# optic_fiber.net
KiCad netlist of a schematic drawn in Altium Designer
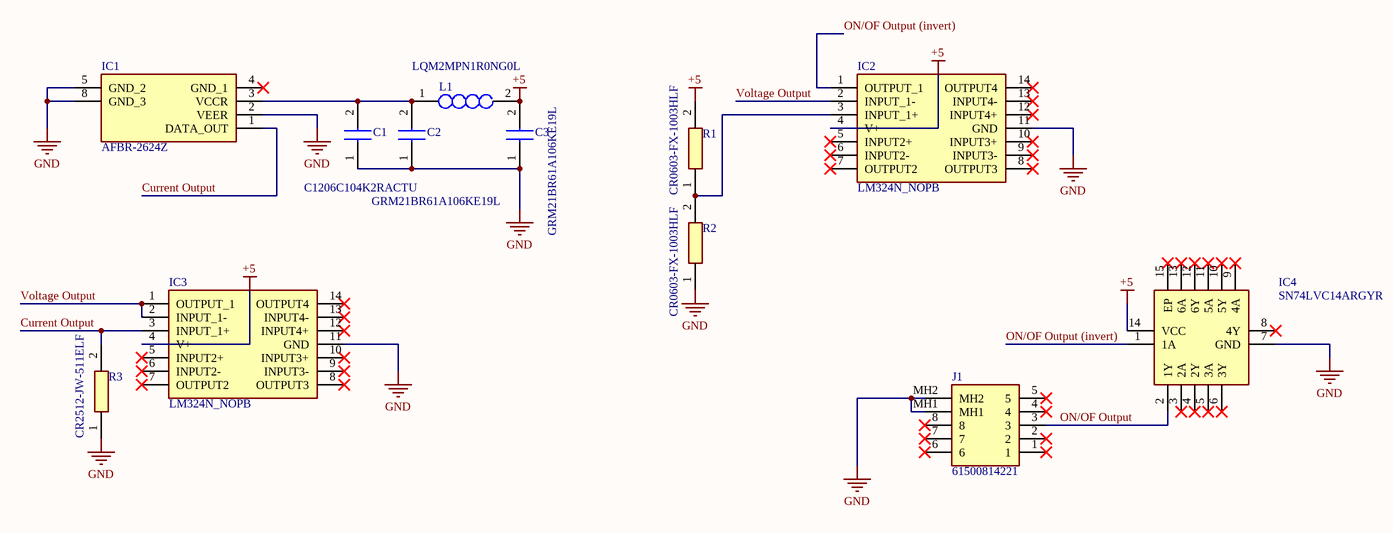
[diagram p0: optic_fiber.SchDoc]

(export (version "E")
  (design (tool "Eeschema 10.0.6"))
  (components
    (comp (ref "C1")
      (value "C1206C104K2RACTU")
      (footprint "optic_fiber:C1206")
      (description "Capacitor")
      (fields (field (name "MOUSER PART NUMBER") "80-C1206C104K2R"))
      (libsource (lib "*") (part "C1206C104K2RACTU"))
    )
    (comp (ref "C2")
      (value "GRM21BR61A106KE19L")
      (footprint "optic_fiber:CAPC2012X145N")
      (description "Capacitor")
      (fields (field (name "MOUSER PART NUMBER") "81-GRM21BR61A106KE19"))
      (libsource (lib "*") (part "GRM21BR61A106KE19L"))
    )
    (comp (ref "C3")
      (value "GRM21BR61A106KE19L")
      (footprint "optic_fiber:CAPC2012X145N")
      (description "Capacitor")
      (fields (field (name "MOUSER PART NUMBER") "81-GRM21BR61A106KE19"))
      (libsource (lib "*") (part "GRM21BR61A106KE19L"))
    )
    (comp (ref "IC1")
      (value "AFBR-2624Z")
      (footprint "optic_fiber:AFBR2624Z")
      (description "Integrated Circuit")
      (fields (field (name "MOUSER PART NUMBER") "630-AFBR-2624Z"))
      (libsource (lib "*") (part "AFBR-2624Z"))
    )
    (comp (ref "IC2")
      (value "LM324N_NOPB")
      (footprint "optic_fiber:DIP794W56P254L1905H533Q14N")
      (description "Integrated Circuit")
      (fields
        (field (name "MANUFACTURER_PART_NUMBER") "LM324N/NOPB")
        (field (name "MOUSER PART NUMBER") "926-LM324N/NOPB")
      )
      (libsource (lib "*") (part "LM324N_NOPB"))
    )
    (comp (ref "IC3")
      (value "LM324N_NOPB")
      (footprint "optic_fiber:DIP794W56P254L1905H533Q14N")
      (description "Integrated Circuit")
      (fields
        (field (name "MANUFACTURER_PART_NUMBER") "LM324N/NOPB")
        (field (name "MOUSER PART NUMBER") "926-LM324N/NOPB")
      )
      (libsource (lib "*") (part "LM324N_NOPB"))
    )
    (comp (ref "IC4")
      (value "SN74LVC14ARGYR")
      (footprint "optic_fiber:RGY-(S-PVQFN-N14)")
      (description "Integrated Circuit")
      (fields (field (name "MOUSER PART NUMBER") "595-SN74LVC14ARGYR"))
      (libsource (lib "*") (part "SN74LVC14ARGYR"))
    )
    (comp (ref "J1")
      (value "61500814221")
      (footprint "optic_fiber:61500814221")
      (description "Connector")
      (fields (field (name "MOUSER PART NUMBER") "710-61500814221"))
      (libsource (lib "*") (part "61500814221"))
    )
    (comp (ref "L1")
      (value "LQM2MPN1R0NG0L")
      (footprint "optic_fiber:LQM2MPN1R0NG0L")
      (description "Inductor")
      (fields (field (name "MOUSER PART NUMBER") "81-LQM2MPN1R0NG0L"))
      (libsource (lib "*") (part "LQM2MPN1R0NG0L"))
    )
    (comp (ref "R1")
      (value "CR0603-FX-1003HLF")
      (footprint "optic_fiber:RESC1608X55N")
      (description "Resistor")
      (fields (field (name "MOUSER PART NUMBER") "652-CR0603-FX1003HLF"))
      (libsource (lib "*") (part "CR0603-FX-1003HLF"))
    )
    (comp (ref "R2")
      (value "CR0603-FX-1003HLF")
      (footprint "optic_fiber:RESC1608X55N")
      (description "Resistor")
      (fields (field (name "MOUSER PART NUMBER") "652-CR0603-FX1003HLF"))
      (libsource (lib "*") (part "CR0603-FX-1003HLF"))
    )
    (comp (ref "R3")
      (value "CR2512-JW-511ELF")
      (footprint "optic_fiber:RESC6331X75N")
      (description "Resistor")
      (fields (field (name "MOUSER PART NUMBER") "652-CR2512-JW-511ELF"))
      (libsource (lib "*") (part "CR2512-JW-511ELF"))
    )
  )
  (nets
    (net (code "1") (name "+5") (class "Default")
      (node (ref "C3") (pin "2") (pinfunction "2_2") (pintype "passive"))
      (node (ref "IC2") (pin "4") (pinfunction "V+_4") (pintype "passive"))
      (node (ref "IC3") (pin "4") (pinfunction "V+_4") (pintype "passive"))
      (node (ref "IC4") (pin "14") (pinfunction "VCC_14") (pintype "passive"))
      (node (ref "L1") (pin "2") (pinfunction "2_2") (pintype "passive"))
      (node (ref "R1") (pin "2") (pinfunction "2_2") (pintype "passive"))
    )
    (net (code "2") (name "/Current Output") (class "Default")
      (node (ref "IC1") (pin "1") (pinfunction "DATA_OUT_1") (pintype "passive"))
      (node (ref "IC3") (pin "3") (pinfunction "INPUT_1+_3") (pintype "passive"))
      (node (ref "R3") (pin "2") (pinfunction "2_2") (pintype "passive"))
    )
    (net (code "3") (name "/ON{slash}OF Output") (class "Default")
      (node (ref "IC4") (pin "2") (pinfunction "1Y_2") (pintype "passive"))
      (node (ref "J1") (pin "3") (pinfunction "3_3") (pintype "passive"))
    )
    (net (code "4") (name "/ON{slash}OF Output (invert)") (class "Default")
      (node (ref "IC2") (pin "1") (pinfunction "OUTPUT_1_1") (pintype "passive"))
      (node (ref "IC4") (pin "1") (pinfunction "1A_1") (pintype "passive"))
    )
    (net (code "5") (name "/Voltage Output") (class "Default")
      (node (ref "IC2") (pin "2") (pinfunction "INPUT_1-_2") (pintype "passive"))
      (node (ref "IC3") (pin "1") (pinfunction "OUTPUT_1_1") (pintype "passive"))
      (node (ref "IC3") (pin "2") (pinfunction "INPUT_1-_2") (pintype "passive"))
    )
    (net (code "6") (name "GND") (class "Default")
      (node (ref "C1") (pin "1") (pinfunction "1_1") (pintype "passive"))
      (node (ref "C2") (pin "1") (pinfunction "1_1") (pintype "passive"))
      (node (ref "C3") (pin "1") (pinfunction "1_1") (pintype "passive"))
      (node (ref "IC1") (pin "2") (pinfunction "VEER_2") (pintype "passive"))
      (node (ref "IC1") (pin "5") (pinfunction "GND_2_5") (pintype "passive"))
      (node (ref "IC1") (pin "8") (pinfunction "GND_3_8") (pintype "passive"))
      (node (ref "IC2") (pin "11") (pinfunction "GND_11") (pintype "passive"))
      (node (ref "IC3") (pin "11") (pinfunction "GND_11") (pintype "passive"))
      (node (ref "IC4") (pin "7") (pinfunction "GND_7") (pintype "passive"))
      (node (ref "J1") (pin "MH1") (pinfunction "MH1_MH1") (pintype "passive"))
      (node (ref "J1") (pin "MH2") (pinfunction "MH2_MH2") (pintype "passive"))
      (node (ref "R2") (pin "1") (pinfunction "1_1") (pintype "passive"))
      (node (ref "R3") (pin "1") (pinfunction "1_1") (pintype "passive"))
    )
    (net (code "7") (name "Net-(IC1-VCCR)") (class "Default")
      (node (ref "C1") (pin "2") (pinfunction "2_2") (pintype "passive"))
      (node (ref "C2") (pin "2") (pinfunction "2_2") (pintype "passive"))
      (node (ref "IC1") (pin "3") (pinfunction "VCCR_3") (pintype "passive"))
      (node (ref "L1") (pin "1") (pinfunction "1_1") (pintype "passive"))
    )
    (net (code "8") (name "Net-(IC2-INPUT_1+)") (class "Default")
      (node (ref "IC2") (pin "3") (pinfunction "INPUT_1+_3") (pintype "passive"))
      (node (ref "R1") (pin "1") (pinfunction "1_1") (pintype "passive"))
      (node (ref "R2") (pin "2") (pinfunction "2_2") (pintype "passive"))
    )
    (net (code "9") (name "unconnected-(IC1-GND_1-Pad4)") (class "Default")
      (node (ref "IC1") (pin "4") (pinfunction "GND_1_4") (pintype "passive+no_connect"))
    )
    (net (code "10") (name "unconnected-(IC2-INPUT2+-Pad5)") (class "Default")
      (node (ref "IC2") (pin "5") (pinfunction "INPUT2+_5") (pintype "passive+no_connect"))
    )
    (net (code "11") (name "unconnected-(IC2-INPUT2--Pad6)") (class "Default")
      (node (ref "IC2") (pin "6") (pinfunction "INPUT2-_6") (pintype "passive+no_connect"))
    )
    (net (code "12") (name "unconnected-(IC2-INPUT3+-Pad10)") (class "Default")
      (node (ref "IC2") (pin "10") (pinfunction "INPUT3+_10") (pintype "passive+no_connect"))
    )
    (net (code "13") (name "unconnected-(IC2-INPUT3--Pad9)") (class "Default")
      (node (ref "IC2") (pin "9") (pinfunction "INPUT3-_9") (pintype "passive+no_connect"))
    )
    (net (code "14") (name "unconnected-(IC2-INPUT4+-Pad12)") (class "Default")
      (node (ref "IC2") (pin "12") (pinfunction "INPUT4+_12") (pintype "passive+no_connect"))
    )
    (net (code "15") (name "unconnected-(IC2-INPUT4--Pad13)") (class "Default")
      (node (ref "IC2") (pin "13") (pinfunction "INPUT4-_13") (pintype "passive+no_connect"))
    )
    (net (code "16") (name "unconnected-(IC2-OUTPUT2-Pad7)") (class "Default")
      (node (ref "IC2") (pin "7") (pinfunction "OUTPUT2_7") (pintype "passive+no_connect"))
    )
    (net (code "17") (name "unconnected-(IC2-OUTPUT3-Pad8)") (class "Default")
      (node (ref "IC2") (pin "8") (pinfunction "OUTPUT3_8") (pintype "passive+no_connect"))
    )
    (net (code "18") (name "unconnected-(IC2-OUTPUT4-Pad14)") (class "Default")
      (node (ref "IC2") (pin "14") (pinfunction "OUTPUT4_14") (pintype "passive+no_connect"))
    )
    (net (code "19") (name "unconnected-(IC3-INPUT2+-Pad5)") (class "Default")
      (node (ref "IC3") (pin "5") (pinfunction "INPUT2+_5") (pintype "passive+no_connect"))
    )
    (net (code "20") (name "unconnected-(IC3-INPUT2--Pad6)") (class "Default")
      (node (ref "IC3") (pin "6") (pinfunction "INPUT2-_6") (pintype "passive+no_connect"))
    )
    (net (code "21") (name "unconnected-(IC3-INPUT3+-Pad10)") (class "Default")
      (node (ref "IC3") (pin "10") (pinfunction "INPUT3+_10") (pintype "passive+no_connect"))
    )
    (net (code "22") (name "unconnected-(IC3-INPUT3--Pad9)") (class "Default")
      (node (ref "IC3") (pin "9") (pinfunction "INPUT3-_9") (pintype "passive+no_connect"))
    )
    (net (code "23") (name "unconnected-(IC3-INPUT4+-Pad12)") (class "Default")
      (node (ref "IC3") (pin "12") (pinfunction "INPUT4+_12") (pintype "passive+no_connect"))
    )
    (net (code "24") (name "unconnected-(IC3-INPUT4--Pad13)") (class "Default")
      (node (ref "IC3") (pin "13") (pinfunction "INPUT4-_13") (pintype "passive+no_connect"))
    )
    (net (code "25") (name "unconnected-(IC3-OUTPUT2-Pad7)") (class "Default")
      (node (ref "IC3") (pin "7") (pinfunction "OUTPUT2_7") (pintype "passive+no_connect"))
    )
    (net (code "26") (name "unconnected-(IC3-OUTPUT3-Pad8)") (class "Default")
      (node (ref "IC3") (pin "8") (pinfunction "OUTPUT3_8") (pintype "passive+no_connect"))
    )
    (net (code "27") (name "unconnected-(IC3-OUTPUT4-Pad14)") (class "Default")
      (node (ref "IC3") (pin "14") (pinfunction "OUTPUT4_14") (pintype "passive+no_connect"))
    )
    (net (code "28") (name "unconnected-(IC4-2A-Pad3)") (class "Default")
      (node (ref "IC4") (pin "3") (pinfunction "2A_3") (pintype "passive+no_connect"))
    )
    (net (code "29") (name "unconnected-(IC4-2Y-Pad4)") (class "Default")
      (node (ref "IC4") (pin "4") (pinfunction "2Y_4") (pintype "passive+no_connect"))
    )
    (net (code "30") (name "unconnected-(IC4-3A-Pad5)") (class "Default")
      (node (ref "IC4") (pin "5") (pinfunction "3A_5") (pintype "passive+no_connect"))
    )
    (net (code "31") (name "unconnected-(IC4-3Y-Pad6)") (class "Default")
      (node (ref "IC4") (pin "6") (pinfunction "3Y_6") (pintype "passive+no_connect"))
    )
    (net (code "32") (name "unconnected-(IC4-4A-Pad9)") (class "Default")
      (node (ref "IC4") (pin "9") (pinfunction "4A_9") (pintype "passive+no_connect"))
    )
    (net (code "33") (name "unconnected-(IC4-4Y-Pad8)") (class "Default")
      (node (ref "IC4") (pin "8") (pinfunction "4Y_8") (pintype "passive+no_connect"))
    )
    (net (code "34") (name "unconnected-(IC4-5A-Pad11)") (class "Default")
      (node (ref "IC4") (pin "11") (pinfunction "5A_11") (pintype "passive+no_connect"))
    )
    (net (code "35") (name "unconnected-(IC4-5Y-Pad10)") (class "Default")
      (node (ref "IC4") (pin "10") (pinfunction "5Y_10") (pintype "passive+no_connect"))
    )
    (net (code "36") (name "unconnected-(IC4-6A-Pad13)") (class "Default")
      (node (ref "IC4") (pin "13") (pinfunction "6A_13") (pintype "passive+no_connect"))
    )
    (net (code "37") (name "unconnected-(IC4-6Y-Pad12)") (class "Default")
      (node (ref "IC4") (pin "12") (pinfunction "6Y_12") (pintype "passive+no_connect"))
    )
    (net (code "38") (name "unconnected-(IC4-EP-Pad15)") (class "Default")
      (node (ref "IC4") (pin "15") (pinfunction "EP_15") (pintype "passive+no_connect"))
    )
    (net (code "39") (name "unconnected-(J1-Pad1)") (class "Default")
      (node (ref "J1") (pin "1") (pinfunction "1_1") (pintype "passive+no_connect"))
    )
    (net (code "40") (name "unconnected-(J1-Pad2)") (class "Default")
      (node (ref "J1") (pin "2") (pinfunction "2_2") (pintype "passive+no_connect"))
    )
    (net (code "41") (name "unconnected-(J1-Pad4)") (class "Default")
      (node (ref "J1") (pin "4") (pinfunction "4_4") (pintype "passive+no_connect"))
    )
    (net (code "42") (name "unconnected-(J1-Pad5)") (class "Default")
      (node (ref "J1") (pin "5") (pinfunction "5_5") (pintype "passive+no_connect"))
    )
    (net (code "43") (name "unconnected-(J1-Pad6)") (class "Default")
      (node (ref "J1") (pin "6") (pinfunction "6_6") (pintype "passive+no_connect"))
    )
    (net (code "44") (name "unconnected-(J1-Pad7)") (class "Default")
      (node (ref "J1") (pin "7") (pinfunction "7_7") (pintype "passive+no_connect"))
    )
    (net (code "45") (name "unconnected-(J1-Pad8)") (class "Default")
      (node (ref "J1") (pin "8") (pinfunction "8_8") (pintype "passive+no_connect"))
    )
  )
)
